# Galileo_Control_Board.net
KiCad netlist of a schematic drawn in Altium Designer
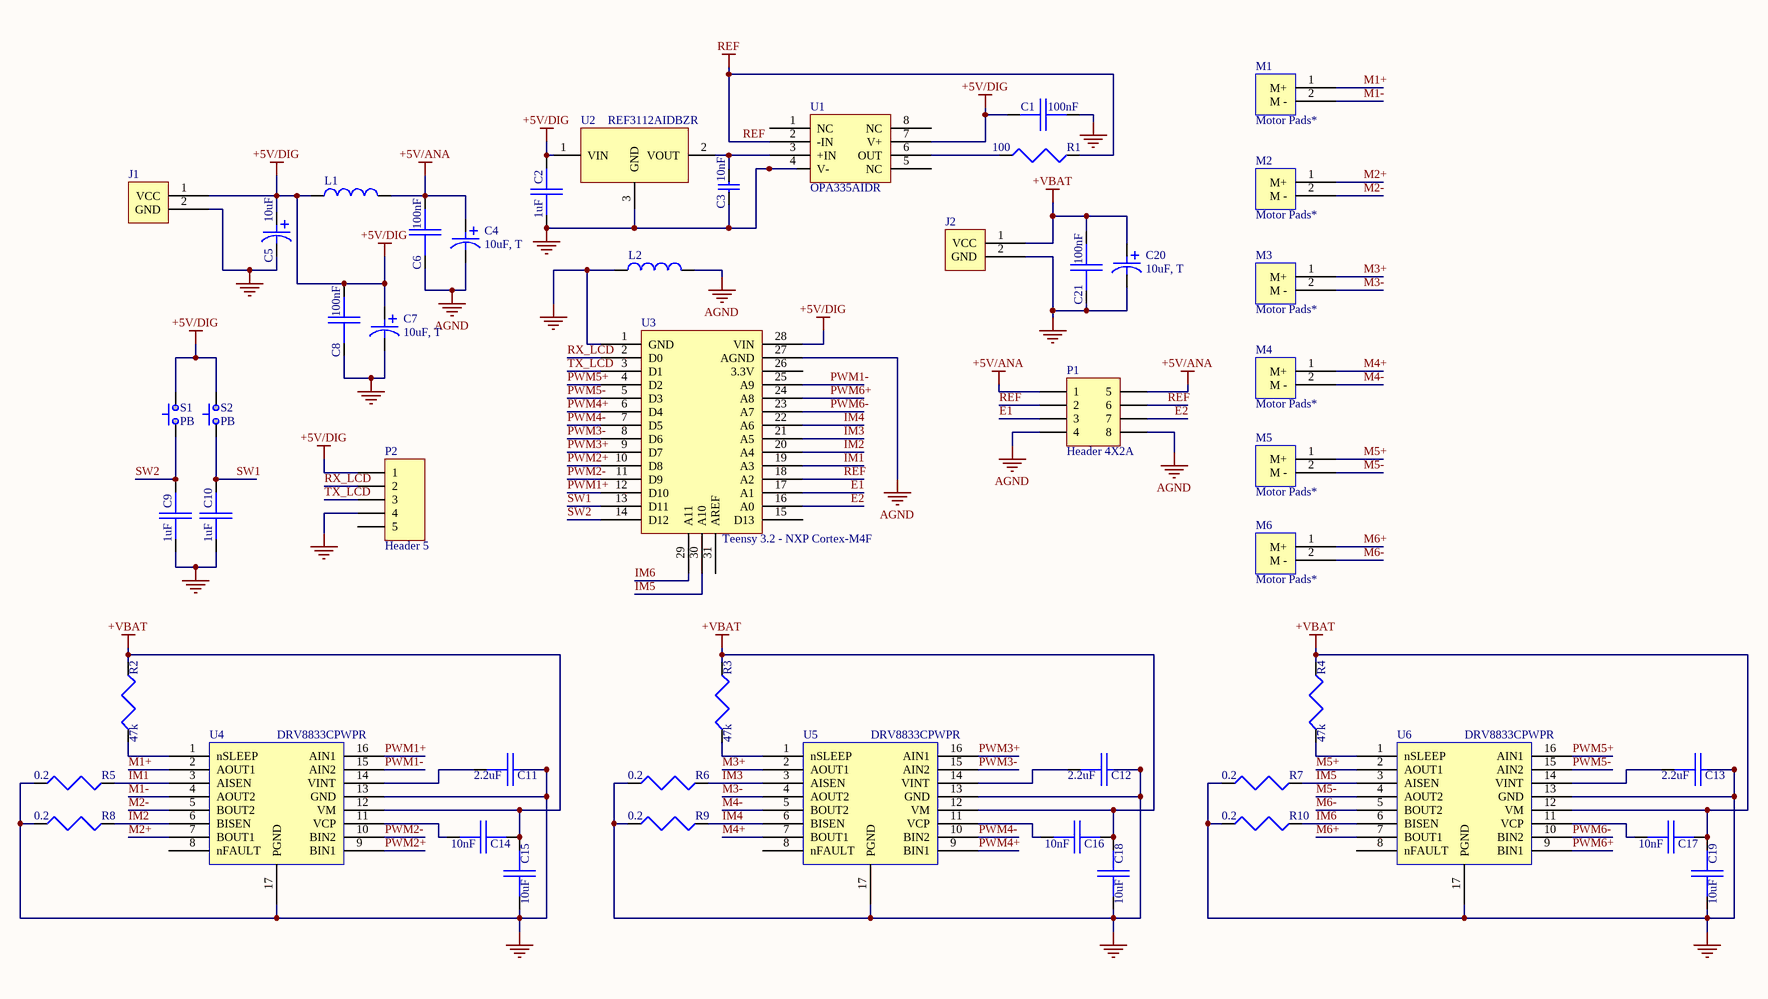
[diagram p0: Galileo_Control_Board.SchDoc]

(export (version "E")
  (design (tool "Eeschema 10.0.6"))
  (components
    (comp (ref "C1")
      (value "100nF")
      (footprint "C0603")
      (description "CAP CER 0.1UF 25V X7R 0603")
      (fields
        (field (name "MANUFACTURER") "Murata Electronics North America")
        (field (name "MANUFACTURER PART NUMBER") "GRM188R71E104KA01D")
      )
      (libsource (lib "EMG") (part "GRM188R71E104KA01D"))
    )
    (comp (ref "C2")
      (value "1uF")
      (footprint "C0603")
      (description "CAP CER 1UF 25V X5R 0603")
      (fields
        (field (name "MANUFACTURER") "Murata Electronics North America")
        (field (name "MANUFACTURER PART NUMBER") "GRM188R61E105KA12D")
      )
      (libsource (lib "EMG") (part "GRM188R61E105KA12D"))
    )
    (comp (ref "C3")
      (value "10nF")
      (footprint "C0805")
      (description "CAP CER 10000PF 50V X7R 0805")
      (fields
        (field (name "MANUFACTURER") "Murata Electronics North America")
        (field (name "MANUFACTURER PART NUMBER") "GRM216R71H103KA01D")
      )
      (libsource (lib "ISL") (part "GRM216R71H103KA01D"))
    )
    (comp (ref "C4")
      (value "10uF, T")
      (footprint "C1206")
      (description "CAP TANT 10UF 20V 10% 2413")
      (fields
        (field (name "MANUFACTURER") "Kemet")
        (field (name "MANUFACTURER PART NUMBER") "T491C106K020AT")
      )
      (libsource (lib "Control") (part "T491C106K020AT"))
    )
    (comp (ref "C5")
      (value "10uF")
      (footprint "CSVB")
      (description "CAP ALUM 10UF 20% 25V SMD")
      (fields
        (field (name "MANUFACTURER") "Panasonic Electronic Components")
        (field (name "MANUFACTURER PART NUMBER") "EEE-1EA100WR")
      )
      (libsource (lib "Control") (part "EEE-1EA100WR"))
    )
    (comp (ref "C6")
      (value "100nF")
      (footprint "C0603")
      (description "CAP CER 0.1UF 25V X7R 0603")
      (fields
        (field (name "MANUFACTURER") "Murata Electronics North America")
        (field (name "MANUFACTURER PART NUMBER") "GRM188R71E104KA01D")
      )
      (libsource (lib "EMG") (part "GRM188R71E104KA01D"))
    )
    (comp (ref "C7")
      (value "10uF, T")
      (footprint "C1206")
      (description "CAP TANT 10UF 20V 10% 2413")
      (fields
        (field (name "MANUFACTURER") "Kemet")
        (field (name "MANUFACTURER PART NUMBER") "T491C106K020AT")
      )
      (libsource (lib "Control") (part "T491C106K020AT"))
    )
    (comp (ref "C8")
      (value "100nF")
      (footprint "C0603")
      (description "CAP CER 0.1UF 25V X7R 0603")
      (fields
        (field (name "MANUFACTURER") "Murata Electronics North America")
        (field (name "MANUFACTURER PART NUMBER") "GRM188R71E104KA01D")
      )
      (libsource (lib "EMG") (part "GRM188R71E104KA01D"))
    )
    (comp (ref "C9")
      (value "1uF")
      (footprint "C0603")
      (description "CAP CER 1UF 25V X5R 0603")
      (fields
        (field (name "MANUFACTURER") "Murata Electronics North America")
        (field (name "MANUFACTURER PART NUMBER") "GRM188R61E105KA12D")
      )
      (libsource (lib "EMG") (part "GRM188R61E105KA12D"))
    )
    (comp (ref "C10")
      (value "1uF")
      (footprint "C0603")
      (description "CAP CER 1UF 25V X5R 0603")
      (fields
        (field (name "MANUFACTURER") "Murata Electronics North America")
        (field (name "MANUFACTURER PART NUMBER") "GRM188R61E105KA12D")
      )
      (libsource (lib "EMG") (part "GRM188R61E105KA12D"))
    )
    (comp (ref "C11")
      (value "2.2uF")
      (footprint "C0603")
      (description "CAP CER 2.2UF 6.3V X5R 0603")
      (fields
        (field (name "MANUFACTURER") "AVX Corporation")
        (field (name "MANUFACTURER PART NUMBER") "06036D225KAT2A")
      )
      (libsource (lib "Galileo_Control_Board") (part "06036D225KAT2A"))
    )
    (comp (ref "C12")
      (value "2.2uF")
      (footprint "C0603")
      (description "CAP CER 2.2UF 6.3V X5R 0603")
      (fields
        (field (name "MANUFACTURER") "AVX Corporation")
        (field (name "MANUFACTURER PART NUMBER") "06036D225KAT2A")
      )
      (libsource (lib "Galileo_Control_Board") (part "06036D225KAT2A"))
    )
    (comp (ref "C13")
      (value "2.2uF")
      (footprint "C0603")
      (description "CAP CER 2.2UF 6.3V X5R 0603")
      (fields
        (field (name "MANUFACTURER") "AVX Corporation")
        (field (name "MANUFACTURER PART NUMBER") "06036D225KAT2A")
      )
      (libsource (lib "Galileo_Control_Board") (part "06036D225KAT2A"))
    )
    (comp (ref "C14")
      (value "10nF")
      (footprint "C0603")
      (description "CAP CER 10000PF 16V X7R 0603")
      (fields
        (field (name "MANUFACTURER") "Kemet")
        (field (name "MANUFACTURER PART NUMBER") "C0603C103K4RACTU")
      )
      (libsource (lib "Galileo_Control_Board") (part "C0603C103K4RACTU"))
    )
    (comp (ref "C15")
      (value "10uF")
      (footprint "C0603")
      (description "CAP CER 10UF 25V X5R 0603")
      (fields
        (field (name "MANUFACTURER") "Murata Electronics North America")
        (field (name "MANUFACTURER PART NUMBER") "GRT188R61E106ME13D")
      )
      (libsource (lib "Galileo_Control_Board") (part "GRT188R61E106ME13D"))
    )
    (comp (ref "C16")
      (value "10nF")
      (footprint "C0603")
      (description "CAP CER 10000PF 16V X7R 0603")
      (fields
        (field (name "MANUFACTURER") "Kemet")
        (field (name "MANUFACTURER PART NUMBER") "C0603C103K4RACTU")
      )
      (libsource (lib "Galileo_Control_Board") (part "C0603C103K4RACTU"))
    )
    (comp (ref "C17")
      (value "10nF")
      (footprint "C0603")
      (description "CAP CER 10000PF 16V X7R 0603")
      (fields
        (field (name "MANUFACTURER") "Kemet")
        (field (name "MANUFACTURER PART NUMBER") "C0603C103K4RACTU")
      )
      (libsource (lib "Galileo_Control_Board") (part "C0603C103K4RACTU"))
    )
    (comp (ref "C18")
      (value "10uF")
      (footprint "C0603")
      (description "CAP CER 10UF 25V X5R 0603")
      (fields
        (field (name "MANUFACTURER") "Murata Electronics North America")
        (field (name "MANUFACTURER PART NUMBER") "GRT188R61E106ME13D")
      )
      (libsource (lib "Galileo_Control_Board") (part "GRT188R61E106ME13D"))
    )
    (comp (ref "C19")
      (value "10uF")
      (footprint "C0603")
      (description "CAP CER 10UF 25V X5R 0603")
      (fields
        (field (name "MANUFACTURER") "Murata Electronics North America")
        (field (name "MANUFACTURER PART NUMBER") "GRT188R61E106ME13D")
      )
      (libsource (lib "Galileo_Control_Board") (part "GRT188R61E106ME13D"))
    )
    (comp (ref "C20")
      (value "10uF, T")
      (footprint "C1206")
      (description "CAP TANT 10UF 20V 10% 2413")
      (fields
        (field (name "MANUFACTURER") "Kemet")
        (field (name "MANUFACTURER PART NUMBER") "T491C106K020AT")
      )
      (libsource (lib "Control") (part "T491C106K020AT"))
    )
    (comp (ref "C21")
      (value "100nF")
      (footprint "C0603")
      (description "CAP CER 0.1UF 25V X7R 0603")
      (fields
        (field (name "MANUFACTURER") "Murata Electronics North America")
        (field (name "MANUFACTURER PART NUMBER") "GRM188R71E104KA01D")
      )
      (libsource (lib "EMG") (part "GRM188R71E104KA01D"))
    )
    (comp (ref "J1")
      (value "TERMINAL BLOCK  2POS 3.5MM")
      (footprint "2POS3.5mm")
      (description "CONN TERMINAL BLOCK 2POS 3.5MM")
      (fields
        (field (name "MANUFACTURER") "Molex, LLC")
        (field (name "MANUFACTURER PART NUMBER") "0393570002")
      )
      (libsource (lib "Control") (part "0393570002"))
    )
    (comp (ref "J2")
      (value "TERMINAL BLOCK  2POS 3.5MM")
      (footprint "2POS3.5mm")
      (description "CONN TERMINAL BLOCK 2POS 3.5MM")
      (fields
        (field (name "MANUFACTURER") "Molex, LLC")
        (field (name "MANUFACTURER PART NUMBER") "0393570002")
      )
      (libsource (lib "Control") (part "0393570002"))
    )
    (comp (ref "L1")
      (value "EMI FILTER BED")
      (footprint "R0603")
      (description "FERRITE BEAD 470 OHM 0603")
      (fields
        (field (name "MANUFACTURER") "Murata Electronics North America")
        (field (name "MANUFACTURER PART NUMBER") "BLM18PG471SN1D")
      )
      (libsource (lib "Control") (part "BLM18PG471SN1D"))
    )
    (comp (ref "L2")
      (value "EMI FILTER BED")
      (footprint "R0603")
      (description "FERRITE BEAD 470 OHM 0603")
      (fields
        (field (name "MANUFACTURER") "Murata Electronics North America")
        (field (name "MANUFACTURER PART NUMBER") "BLM18PG471SN1D")
      )
      (libsource (lib "Control") (part "BLM18PG471SN1D"))
    )
    (comp (ref "M1")
      (value "Motor Pads*")
      (footprint "Motor_PAD")
      (fields
        (field (name "MANUFACTURER") "Portescap")
        (field (name "MANUFACTURER PART NUMBER") "22N1R78313P1001")
      )
      (libsource (lib "Galileo_Control_Board") (part "Motor_PADs"))
    )
    (comp (ref "M2")
      (value "Motor Pads*")
      (footprint "Motor_PAD")
      (fields
        (field (name "MANUFACTURER") "Portescap")
        (field (name "MANUFACTURER PART NUMBER") "22N1R78313P1001")
      )
      (libsource (lib "Galileo_Control_Board") (part "Motor_PADs"))
    )
    (comp (ref "M3")
      (value "Motor Pads*")
      (footprint "Motor_PAD")
      (fields
        (field (name "MANUFACTURER") "Portescap")
        (field (name "MANUFACTURER PART NUMBER") "22N1R78313P1001")
      )
      (libsource (lib "Galileo_Control_Board") (part "Motor_PADs"))
    )
    (comp (ref "M4")
      (value "Motor Pads*")
      (footprint "Motor_PAD")
      (fields
        (field (name "MANUFACTURER") "Portescap")
        (field (name "MANUFACTURER PART NUMBER") "22N1R78313P1001")
      )
      (libsource (lib "Galileo_Control_Board") (part "Motor_PADs"))
    )
    (comp (ref "M5")
      (value "Motor Pads*")
      (footprint "Motor_PAD")
      (fields
        (field (name "MANUFACTURER") "Portescap")
        (field (name "MANUFACTURER PART NUMBER") "22N1R78313P1001")
      )
      (libsource (lib "Galileo_Control_Board") (part "Motor_PADs"))
    )
    (comp (ref "M6")
      (value "Motor Pads*")
      (footprint "Motor_PAD")
      (fields
        (field (name "MANUFACTURER") "Portescap")
        (field (name "MANUFACTURER PART NUMBER") "22N1R78313P1001")
      )
      (libsource (lib "Galileo_Control_Board") (part "Motor_PADs"))
    )
    (comp (ref "P1")
      (value "Header 4X2A")
      (footprint "HDR2X4_CEN")
      (description "Header, 4-Pin, Dual row")
      (fields (field (name "PUBLISHER") "Altium Limited"))
      (libsource (lib "Miscellaneous Connectors") (part "Header 4X2A"))
    )
    (comp (ref "P2")
      (value "Header 5")
      (footprint "HDR1X5")
      (description "Header, 5-Pin")
      (fields (field (name "PUBLISHER") "Altium Limited"))
      (libsource (lib "Miscellaneous Connectors") (part "Header 5"))
    )
    (comp (ref "R1")
      (value "100")
      (footprint "R0603")
      (description "RES SMD 100 OHM 1% 1/10W 0603")
      (fields
        (field (name "MANUFACTURER") "Panasonic Electronic Components")
        (field (name "MANUFACTURER PART NUMBER") "ERJ-3EKF1000V")
      )
      (libsource (lib "EMG") (part "ERJ-3EKF1000V"))
    )
    (comp (ref "R2")
      (value "47k")
      (footprint "R0603")
      (description "RES SMD 47K OHM 1% 1/10W 0603")
      (fields
        (field (name "MANUFACTURER") "Panasonic Electronic Components")
        (field (name "MANUFACTURER PART NUMBER") "ERJ-3EKF4702V")
      )
      (libsource (lib "Galileo_Control_Board") (part "ERJ-3EKF4702V"))
    )
    (comp (ref "R3")
      (value "47k")
      (footprint "R0603")
      (description "RES SMD 47K OHM 1% 1/10W 0603")
      (fields
        (field (name "MANUFACTURER") "Panasonic Electronic Components")
        (field (name "MANUFACTURER PART NUMBER") "ERJ-3EKF4702V")
      )
      (libsource (lib "Galileo_Control_Board") (part "ERJ-3EKF4702V"))
    )
    (comp (ref "R4")
      (value "47k")
      (footprint "R0603")
      (description "RES SMD 47K OHM 1% 1/10W 0603")
      (fields
        (field (name "MANUFACTURER") "Panasonic Electronic Components")
        (field (name "MANUFACTURER PART NUMBER") "ERJ-3EKF4702V")
      )
      (libsource (lib "Galileo_Control_Board") (part "ERJ-3EKF4702V"))
    )
    (comp (ref "R5")
      (value "0.2")
      (footprint "R1206")
      (description "RES SMD 0.2 OHM 5% 1/2W 1206")
      (fields
        (field (name "MANUFACTURER") "Panasonic Electronic Components")
        (field (name "MANUFACTURER PART NUMBER") "ERJ-8BSJR20V")
      )
      (libsource (lib "Galileo_Control_Board") (part "ERJ-8BSJR20V"))
    )
    (comp (ref "R6")
      (value "0.2")
      (footprint "R1206")
      (description "RES SMD 0.2 OHM 5% 1/2W 1206")
      (fields
        (field (name "MANUFACTURER") "Panasonic Electronic Components")
        (field (name "MANUFACTURER PART NUMBER") "ERJ-8BSJR20V")
      )
      (libsource (lib "Galileo_Control_Board") (part "ERJ-8BSJR20V"))
    )
    (comp (ref "R7")
      (value "0.2")
      (footprint "R1206")
      (description "RES SMD 0.2 OHM 5% 1/2W 1206")
      (fields
        (field (name "MANUFACTURER") "Panasonic Electronic Components")
        (field (name "MANUFACTURER PART NUMBER") "ERJ-8BSJR20V")
      )
      (libsource (lib "Galileo_Control_Board") (part "ERJ-8BSJR20V"))
    )
    (comp (ref "R8")
      (value "0.2")
      (footprint "R1206")
      (description "RES SMD 0.2 OHM 5% 1/2W 1206")
      (fields
        (field (name "MANUFACTURER") "Panasonic Electronic Components")
        (field (name "MANUFACTURER PART NUMBER") "ERJ-8BSJR20V")
      )
      (libsource (lib "Galileo_Control_Board") (part "ERJ-8BSJR20V"))
    )
    (comp (ref "R9")
      (value "0.2")
      (footprint "R1206")
      (description "RES SMD 0.2 OHM 5% 1/2W 1206")
      (fields
        (field (name "MANUFACTURER") "Panasonic Electronic Components")
        (field (name "MANUFACTURER PART NUMBER") "ERJ-8BSJR20V")
      )
      (libsource (lib "Galileo_Control_Board") (part "ERJ-8BSJR20V"))
    )
    (comp (ref "R10")
      (value "0.2")
      (footprint "R1206")
      (description "RES SMD 0.2 OHM 5% 1/2W 1206")
      (fields
        (field (name "MANUFACTURER") "Panasonic Electronic Components")
        (field (name "MANUFACTURER PART NUMBER") "ERJ-8BSJR20V")
      )
      (libsource (lib "Galileo_Control_Board") (part "ERJ-8BSJR20V"))
    )
    (comp (ref "S1")
      (value "PB")
      (footprint "SW")
      (description "SWITCH PUSH SPST-NO 0.1A 32V")
      (fields
        (field (name "MANUFACTURER") "C&K Components")
        (field (name "MANUFACTURER PART NUMBER") "D6C90 F1 LFS")
      )
      (libsource (lib "Control") (part "D6C90 F1 LFS"))
    )
    (comp (ref "S2")
      (value "PB")
      (footprint "SW")
      (description "SWITCH PUSH SPST-NO 0.1A 32V")
      (fields
        (field (name "MANUFACTURER") "C&K Components")
        (field (name "MANUFACTURER PART NUMBER") "D6C90 F1 LFS")
      )
      (libsource (lib "Control") (part "D6C90 F1 LFS"))
    )
    (comp (ref "U1")
      (value "OPA335AIDR")
      (footprint "SO-8")
      (description "IC OPAMP CHOPPER 2MHZ RRO 8SOIC")
      (fields (field (name "MANUFACTURER") "Texas Instruments"))
      (libsource (lib "DCDC") (part "OPA335AIDR"))
    )
    (comp (ref "U2")
      (value "REF3112AIDBZR")
      (footprint "SOT-23")
      (description "IC VREF SERIES 1.25V SOT23-3")
      (fields (field (name "MANUFACTURER") "Texas Instruments") (field (name "TOLERANCE") "±0.2%"))
      (libsource (lib "DCDC") (part "REF3112AIDBZR"))
    )
    (comp (ref "U3")
      (value "Teensy 3.2 - NXP Cortex-M4F")
      (footprint "DIP28")
      (fields
        (field (name "MANUFACTURER") "SparkFun Electronics")
        (field (name "MANUFACTURER PART NUMBER") "DEV-13305")
      )
      (libsource (lib "Control") (part "Teensy"))
    )
    (comp (ref "U4")
      (value "DRV8833CPWPR")
      (footprint "SOP16")
      (description "IC MOTOR DRIVER PAR")
      (fields (field (name "MANUFACTURER") "Texas Instruments"))
      (libsource (lib "Galileo_Control_Board") (part "DRV8833CPWPR"))
    )
    (comp (ref "U5")
      (value "DRV8833CPWPR")
      (footprint "SOP16")
      (description "IC MOTOR DRIVER PAR")
      (fields (field (name "MANUFACTURER") "Texas Instruments"))
      (libsource (lib "Galileo_Control_Board") (part "DRV8833CPWPR"))
    )
    (comp (ref "U6")
      (value "DRV8833CPWPR")
      (footprint "SOP16")
      (description "IC MOTOR DRIVER PAR")
      (fields (field (name "MANUFACTURER") "Texas Instruments"))
      (libsource (lib "Galileo_Control_Board") (part "DRV8833CPWPR"))
    )
  )
  (nets
    (net (code "1") (name "+5V{slash}ANA") (class "Default")
      (node (ref "C4") (pin "1") (pinfunction "1_1") (pintype "passive"))
      (node (ref "C6") (pin "2") (pinfunction "2_2") (pintype "passive"))
      (node (ref "L1") (pin "2") (pinfunction "2_2") (pintype "passive"))
      (node (ref "P1") (pin "1") (pinfunction "1_1") (pintype "passive"))
      (node (ref "P1") (pin "5") (pinfunction "5_5") (pintype "passive"))
    )
    (net (code "2") (name "+5V{slash}DIG") (class "Default")
      (node (ref "C1") (pin "2") (pinfunction "2_2") (pintype "passive"))
      (node (ref "C2") (pin "2") (pinfunction "2_2") (pintype "passive"))
      (node (ref "C5") (pin "1") (pinfunction "1_1") (pintype "passive"))
      (node (ref "C7") (pin "1") (pinfunction "1_1") (pintype "passive"))
      (node (ref "C8") (pin "2") (pinfunction "2_2") (pintype "passive"))
      (node (ref "J1") (pin "1") (pinfunction "VCC_1") (pintype "passive"))
      (node (ref "L1") (pin "1") (pinfunction "1_1") (pintype "passive"))
      (node (ref "P2") (pin "1") (pinfunction "1_1") (pintype "passive"))
      (node (ref "S1") (pin "2") (pinfunction "2_2") (pintype "passive"))
      (node (ref "S2") (pin "2") (pinfunction "2_2") (pintype "passive"))
      (node (ref "U1") (pin "7") (pinfunction "V+_7") (pintype "passive"))
      (node (ref "U2") (pin "1") (pinfunction "VIN_1") (pintype "passive"))
      (node (ref "U3") (pin "28") (pinfunction "VIN_28") (pintype "passive"))
    )
    (net (code "3") (name "+VBAT") (class "Default")
      (node (ref "C14") (pin "2") (pinfunction "2_2") (pintype "passive"))
      (node (ref "C15") (pin "2") (pinfunction "2_2") (pintype "passive"))
      (node (ref "C16") (pin "2") (pinfunction "2_2") (pintype "passive"))
      (node (ref "C17") (pin "2") (pinfunction "2_2") (pintype "passive"))
      (node (ref "C18") (pin "2") (pinfunction "2_2") (pintype "passive"))
      (node (ref "C19") (pin "2") (pinfunction "2_2") (pintype "passive"))
      (node (ref "C20") (pin "1") (pinfunction "1_1") (pintype "passive"))
      (node (ref "C21") (pin "2") (pinfunction "2_2") (pintype "passive"))
      (node (ref "J2") (pin "1") (pinfunction "VCC_1") (pintype "passive"))
      (node (ref "R2") (pin "2") (pinfunction "2_2") (pintype "passive"))
      (node (ref "R3") (pin "2") (pinfunction "2_2") (pintype "passive"))
      (node (ref "R4") (pin "2") (pinfunction "2_2") (pintype "passive"))
      (node (ref "U4") (pin "12") (pinfunction "VM_12") (pintype "passive"))
      (node (ref "U5") (pin "12") (pinfunction "VM_12") (pintype "passive"))
      (node (ref "U6") (pin "12") (pinfunction "VM_12") (pintype "passive"))
    )
    (net (code "4") (name "/E1") (class "Default")
      (node (ref "P1") (pin "3") (pinfunction "3_3") (pintype "passive"))
      (node (ref "U3") (pin "17") (pinfunction "A1_17") (pintype "passive"))
    )
    (net (code "5") (name "/E2") (class "Default")
      (node (ref "P1") (pin "7") (pinfunction "7_7") (pintype "passive"))
      (node (ref "U3") (pin "16") (pinfunction "A0_16") (pintype "passive"))
    )
    (net (code "6") (name "/IM1") (class "Default")
      (node (ref "R5") (pin "2") (pinfunction "2_2") (pintype "passive"))
      (node (ref "U3") (pin "19") (pinfunction "A3_19") (pintype "passive"))
      (node (ref "U4") (pin "3") (pinfunction "AISEN_3") (pintype "passive"))
    )
    (net (code "7") (name "/IM2") (class "Default")
      (node (ref "R8") (pin "2") (pinfunction "2_2") (pintype "passive"))
      (node (ref "U3") (pin "20") (pinfunction "A4_20") (pintype "passive"))
      (node (ref "U4") (pin "6") (pinfunction "BISEN_6") (pintype "passive"))
    )
    (net (code "8") (name "/IM3") (class "Default")
      (node (ref "R6") (pin "2") (pinfunction "2_2") (pintype "passive"))
      (node (ref "U3") (pin "21") (pinfunction "A5_21") (pintype "passive"))
      (node (ref "U5") (pin "3") (pinfunction "AISEN_3") (pintype "passive"))
    )
    (net (code "9") (name "/IM4") (class "Default")
      (node (ref "R9") (pin "2") (pinfunction "2_2") (pintype "passive"))
      (node (ref "U3") (pin "22") (pinfunction "A6_22") (pintype "passive"))
      (node (ref "U5") (pin "6") (pinfunction "BISEN_6") (pintype "passive"))
    )
    (net (code "10") (name "/IM5") (class "Default")
      (node (ref "R7") (pin "2") (pinfunction "2_2") (pintype "passive"))
      (node (ref "U3") (pin "30") (pinfunction "A10_30") (pintype "passive"))
      (node (ref "U6") (pin "3") (pinfunction "AISEN_3") (pintype "passive"))
    )
    (net (code "11") (name "/IM6") (class "Default")
      (node (ref "R10") (pin "2") (pinfunction "2_2") (pintype "passive"))
      (node (ref "U3") (pin "29") (pinfunction "A11_29") (pintype "passive"))
      (node (ref "U6") (pin "6") (pinfunction "BISEN_6") (pintype "passive"))
    )
    (net (code "12") (name "/M1+") (class "Default")
      (node (ref "M1") (pin "1") (pinfunction "M+_1") (pintype "passive"))
      (node (ref "U4") (pin "2") (pinfunction "AOUT1_2") (pintype "passive"))
    )
    (net (code "13") (name "/M1-") (class "Default")
      (node (ref "M1") (pin "2") (pinfunction "M_-_2") (pintype "passive"))
      (node (ref "U4") (pin "4") (pinfunction "AOUT2_4") (pintype "passive"))
    )
    (net (code "14") (name "/M2+") (class "Default")
      (node (ref "M2") (pin "1") (pinfunction "M+_1") (pintype "passive"))
      (node (ref "U4") (pin "7") (pinfunction "BOUT1_7") (pintype "passive"))
    )
    (net (code "15") (name "/M2-") (class "Default")
      (node (ref "M2") (pin "2") (pinfunction "M_-_2") (pintype "passive"))
      (node (ref "U4") (pin "5") (pinfunction "BOUT2_5") (pintype "passive"))
    )
    (net (code "16") (name "/M3+") (class "Default")
      (node (ref "M3") (pin "1") (pinfunction "M+_1") (pintype "passive"))
      (node (ref "U5") (pin "2") (pinfunction "AOUT1_2") (pintype "passive"))
    )
    (net (code "17") (name "/M3-") (class "Default")
      (node (ref "M3") (pin "2") (pinfunction "M_-_2") (pintype "passive"))
      (node (ref "U5") (pin "4") (pinfunction "AOUT2_4") (pintype "passive"))
    )
    (net (code "18") (name "/M4+") (class "Default")
      (node (ref "M4") (pin "1") (pinfunction "M+_1") (pintype "passive"))
      (node (ref "U5") (pin "7") (pinfunction "BOUT1_7") (pintype "passive"))
    )
    (net (code "19") (name "/M4-") (class "Default")
      (node (ref "M4") (pin "2") (pinfunction "M_-_2") (pintype "passive"))
      (node (ref "U5") (pin "5") (pinfunction "BOUT2_5") (pintype "passive"))
    )
    (net (code "20") (name "/M5+") (class "Default")
      (node (ref "M5") (pin "1") (pinfunction "M+_1") (pintype "passive"))
      (node (ref "U6") (pin "2") (pinfunction "AOUT1_2") (pintype "passive"))
    )
    (net (code "21") (name "/M5-") (class "Default")
      (node (ref "M5") (pin "2") (pinfunction "M_-_2") (pintype "passive"))
      (node (ref "U6") (pin "4") (pinfunction "AOUT2_4") (pintype "passive"))
    )
    (net (code "22") (name "/M6+") (class "Default")
      (node (ref "M6") (pin "1") (pinfunction "M+_1") (pintype "passive"))
      (node (ref "U6") (pin "7") (pinfunction "BOUT1_7") (pintype "passive"))
    )
    (net (code "23") (name "/M6-") (class "Default")
      (node (ref "M6") (pin "2") (pinfunction "M_-_2") (pintype "passive"))
      (node (ref "U6") (pin "5") (pinfunction "BOUT2_5") (pintype "passive"))
    )
    (net (code "24") (name "/PWM1+") (class "Default")
      (node (ref "U3") (pin "12") (pinfunction "D10_12") (pintype "passive"))
      (node (ref "U4") (pin "16") (pinfunction "AIN1_16") (pintype "passive"))
    )
    (net (code "25") (name "/PWM1-") (class "Default")
      (node (ref "U3") (pin "25") (pinfunction "A9_25") (pintype "passive"))
      (node (ref "U4") (pin "15") (pinfunction "AIN2_15") (pintype "passive"))
    )
    (net (code "26") (name "/PWM2+") (class "Default")
      (node (ref "U3") (pin "10") (pinfunction "D8_10") (pintype "passive"))
      (node (ref "U4") (pin "9") (pinfunction "BIN1_9") (pintype "passive"))
    )
    (net (code "27") (name "/PWM2-") (class "Default")
      (node (ref "U3") (pin "11") (pinfunction "D9_11") (pintype "passive"))
      (node (ref "U4") (pin "10") (pinfunction "BIN2_10") (pintype "passive"))
    )
    (net (code "28") (name "/PWM3+") (class "Default")
      (node (ref "U3") (pin "9") (pinfunction "D7_9") (pintype "passive"))
      (node (ref "U5") (pin "16") (pinfunction "AIN1_16") (pintype "passive"))
    )
    (net (code "29") (name "/PWM3-") (class "Default")
      (node (ref "U3") (pin "8") (pinfunction "D6_8") (pintype "passive"))
      (node (ref "U5") (pin "15") (pinfunction "AIN2_15") (pintype "passive"))
    )
    (net (code "30") (name "/PWM4+") (class "Default")
      (node (ref "U3") (pin "6") (pinfunction "D4_6") (pintype "passive"))
      (node (ref "U5") (pin "9") (pinfunction "BIN1_9") (pintype "passive"))
    )
    (net (code "31") (name "/PWM4-") (class "Default")
      (node (ref "U3") (pin "7") (pinfunction "D5_7") (pintype "passive"))
      (node (ref "U5") (pin "10") (pinfunction "BIN2_10") (pintype "passive"))
    )
    (net (code "32") (name "/PWM5+") (class "Default")
      (node (ref "U3") (pin "4") (pinfunction "D2_4") (pintype "passive"))
      (node (ref "U6") (pin "16") (pinfunction "AIN1_16") (pintype "passive"))
    )
    (net (code "33") (name "/PWM5-") (class "Default")
      (node (ref "U3") (pin "5") (pinfunction "D3_5") (pintype "passive"))
      (node (ref "U6") (pin "15") (pinfunction "AIN2_15") (pintype "passive"))
    )
    (net (code "34") (name "/PWM6+") (class "Default")
      (node (ref "U3") (pin "24") (pinfunction "A8_24") (pintype "passive"))
      (node (ref "U6") (pin "9") (pinfunction "BIN1_9") (pintype "passive"))
    )
    (net (code "35") (name "/PWM6-") (class "Default")
      (node (ref "U3") (pin "23") (pinfunction "A7_23") (pintype "passive"))
      (node (ref "U6") (pin "10") (pinfunction "BIN2_10") (pintype "passive"))
    )
    (net (code "36") (name "/RX_LCD") (class "Default")
      (node (ref "P2") (pin "2") (pinfunction "2_2") (pintype "passive"))
      (node (ref "U3") (pin "2") (pinfunction "D0_2") (pintype "passive"))
    )
    (net (code "37") (name "/SW1") (class "Default")
      (node (ref "C10") (pin "2") (pinfunction "2_2") (pintype "passive"))
      (node (ref "S2") (pin "1") (pinfunction "1_1") (pintype "passive"))
      (node (ref "U3") (pin "13") (pinfunction "D11_13") (pintype "passive"))
    )
    (net (code "38") (name "/SW2") (class "Default")
      (node (ref "C9") (pin "2") (pinfunction "2_2") (pintype "passive"))
      (node (ref "S1") (pin "1") (pinfunction "1_1") (pintype "passive"))
      (node (ref "U3") (pin "14") (pinfunction "D12_14") (pintype "passive"))
    )
    (net (code "39") (name "/TX_LCD") (class "Default")
      (node (ref "P2") (pin "3") (pinfunction "3_3") (pintype "passive"))
      (node (ref "U3") (pin "3") (pinfunction "D1_3") (pintype "passive"))
    )
    (net (code "40") (name "AGND") (class "Default")
      (node (ref "C4") (pin "2") (pinfunction "2_2") (pintype "passive"))
      (node (ref "C6") (pin "1") (pinfunction "1_1") (pintype "passive"))
      (node (ref "L2") (pin "2") (pinfunction "2_2") (pintype "passive"))
      (node (ref "P1") (pin "4") (pinfunction "4_4") (pintype "passive"))
      (node (ref "P1") (pin "8") (pinfunction "8_8") (pintype "passive"))
      (node (ref "U3") (pin "27") (pinfunction "AGND_27") (pintype "passive"))
    )
    (net (code "41") (name "GND") (class "Default")
      (node (ref "C1") (pin "1") (pinfunction "1_1") (pintype "passive"))
      (node (ref "C10") (pin "1") (pinfunction "1_1") (pintype "passive"))
      (node (ref "C11") (pin "2") (pinfunction "2_2") (pintype "passive"))
      (node (ref "C12") (pin "2") (pinfunction "2_2") (pintype "passive"))
      (node (ref "C13") (pin "2") (pinfunction "2_2") (pintype "passive"))
      (node (ref "C15") (pin "1") (pinfunction "1_1") (pintype "passive"))
      (node (ref "C18") (pin "1") (pinfunction "1_1") (pintype "passive"))
      (node (ref "C19") (pin "1") (pinfunction "1_1") (pintype "passive"))
      (node (ref "C2") (pin "1") (pinfunction "1_1") (pintype "passive"))
      (node (ref "C20") (pin "2") (pinfunction "2_2") (pintype "passive"))
      (node (ref "C21") (pin "1") (pinfunction "1_1") (pintype "passive"))
      (node (ref "C3") (pin "1") (pinfunction "1_1") (pintype "passive"))
      (node (ref "C5") (pin "2") (pinfunction "2_2") (pintype "passive"))
      (node (ref "C7") (pin "2") (pinfunction "2_2") (pintype "passive"))
      (node (ref "C8") (pin "1") (pinfunction "1_1") (pintype "passive"))
      (node (ref "C9") (pin "1") (pinfunction "1_1") (pintype "passive"))
      (node (ref "J1") (pin "2") (pinfunction "GND_2") (pintype "passive"))
      (node (ref "J2") (pin "2") (pinfunction "GND_2") (pintype "passive"))
      (node (ref "L2") (pin "1") (pinfunction "1_1") (pintype "passive"))
      (node (ref "P2") (pin "4") (pinfunction "4_4") (pintype "passive"))
      (node (ref "R10") (pin "1") (pinfunction "1_1") (pintype "passive"))
      (node (ref "R5") (pin "1") (pinfunction "1_1") (pintype "passive"))
      (node (ref "R6") (pin "1") (pinfunction "1_1") (pintype "passive"))
      (node (ref "R7") (pin "1") (pinfunction "1_1") (pintype "passive"))
      (node (ref "R8") (pin "1") (pinfunction "1_1") (pintype "passive"))
      (node (ref "R9") (pin "1") (pinfunction "1_1") (pintype "passive"))
      (node (ref "U1") (pin "4") (pinfunction "V-_4") (pintype "passive"))
      (node (ref "U2") (pin "3") (pinfunction "GND_3") (pintype "passive"))
      (node (ref "U3") (pin "1") (pinfunction "GND_1") (pintype "passive"))
      (node (ref "U4") (pin "13") (pinfunction "GND_13") (pintype "passive"))
      (node (ref "U4") (pin "17") (pinfunction "PGND_17") (pintype "passive"))
      (node (ref "U5") (pin "13") (pinfunction "GND_13") (pintype "passive"))
      (node (ref "U5") (pin "17") (pinfunction "PGND_17") (pintype "passive"))
      (node (ref "U6") (pin "13") (pinfunction "GND_13") (pintype "passive"))
      (node (ref "U6") (pin "17") (pinfunction "PGND_17") (pintype "passive"))
    )
    (net (code "42") (name "Net-(U1-+IN)") (class "Default")
      (node (ref "C3") (pin "2") (pinfunction "2_2") (pintype "passive"))
      (node (ref "U1") (pin "3") (pinfunction "+IN_3") (pintype "passive"))
      (node (ref "U2") (pin "2") (pinfunction "VOUT_2") (pintype "passive"))
    )
    (net (code "43") (name "Net-(U1-OUT)") (class "Default")
      (node (ref "R1") (pin "2") (pinfunction "2_2") (pintype "passive"))
      (node (ref "U1") (pin "6") (pinfunction "OUT_6") (pintype "passive"))
    )
    (net (code "44") (name "Net-(U4-VCP)") (class "Default")
      (node (ref "C14") (pin "1") (pinfunction "1_1") (pintype "passive"))
      (node (ref "U4") (pin "11") (pinfunction "VCP_11") (pintype "passive"))
    )
    (net (code "45") (name "Net-(U4-VINT)") (class "Default")
      (node (ref "C11") (pin "1") (pinfunction "1_1") (pintype "passive"))
      (node (ref "U4") (pin "14") (pinfunction "VINT_14") (pintype "passive"))
    )
    (net (code "46") (name "Net-(U4-nSLEEP)") (class "Default")
      (node (ref "R2") (pin "1") (pinfunction "1_1") (pintype "passive"))
      (node (ref "U4") (pin "1") (pinfunction "nSLEEP_1") (pintype "passive"))
    )
    (net (code "47") (name "Net-(U5-VCP)") (class "Default")
      (node (ref "C16") (pin "1") (pinfunction "1_1") (pintype "passive"))
      (node (ref "U5") (pin "11") (pinfunction "VCP_11") (pintype "passive"))
    )
    (net (code "48") (name "Net-(U5-VINT)") (class "Default")
      (node (ref "C12") (pin "1") (pinfunction "1_1") (pintype "passive"))
      (node (ref "U5") (pin "14") (pinfunction "VINT_14") (pintype "passive"))
    )
    (net (code "49") (name "Net-(U5-nSLEEP)") (class "Default")
      (node (ref "R3") (pin "1") (pinfunction "1_1") (pintype "passive"))
      (node (ref "U5") (pin "1") (pinfunction "nSLEEP_1") (pintype "passive"))
    )
    (net (code "50") (name "Net-(U6-VCP)") (class "Default")
      (node (ref "C17") (pin "1") (pinfunction "1_1") (pintype "passive"))
      (node (ref "U6") (pin "11") (pinfunction "VCP_11") (pintype "passive"))
    )
    (net (code "51") (name "Net-(U6-VINT)") (class "Default")
      (node (ref "C13") (pin "1") (pinfunction "1_1") (pintype "passive"))
      (node (ref "U6") (pin "14") (pinfunction "VINT_14") (pintype "passive"))
    )
    (net (code "52") (name "Net-(U6-nSLEEP)") (class "Default")
      (node (ref "R4") (pin "1") (pinfunction "1_1") (pintype "passive"))
      (node (ref "U6") (pin "1") (pinfunction "nSLEEP_1") (pintype "passive"))
    )
    (net (code "53") (name "REF") (class "Default")
      (node (ref "P1") (pin "2") (pinfunction "2_2") (pintype "passive"))
      (node (ref "P1") (pin "6") (pinfunction "6_6") (pintype "passive"))
      (node (ref "R1") (pin "1") (pinfunction "1_1") (pintype "passive"))
      (node (ref "U1") (pin "2") (pinfunction "-IN_2") (pintype "passive"))
      (node (ref "U3") (pin "18") (pinfunction "A2_18") (pintype "passive"))
    )
    (net (code "54") (name "unconnected-(P2-Pad5)") (class "Default")
      (node (ref "P2") (pin "5") (pinfunction "5_5") (pintype "passive"))
    )
    (net (code "55") (name "unconnected-(U1-NC-Pad1)") (class "Default")
      (node (ref "U1") (pin "1") (pinfunction "NC_1") (pintype "passive"))
    )
    (net (code "56") (name "unconnected-(U1-NC-Pad5)") (class "Default")
      (node (ref "U1") (pin "5") (pinfunction "NC_5") (pintype "passive"))
    )
    (net (code "57") (name "unconnected-(U1-NC-Pad8)") (class "Default")
      (node (ref "U1") (pin "8") (pinfunction "NC_8") (pintype "passive"))
    )
    (net (code "58") (name "unconnected-(U3-3.3V-Pad26)") (class "Default")
      (node (ref "U3") (pin "26") (pinfunction "3.3V_26") (pintype "passive"))
    )
    (net (code "59") (name "unconnected-(U3-AREF-Pad31)") (class "Default")
      (node (ref "U3") (pin "31") (pinfunction "AREF_31") (pintype "passive"))
    )
    (net (code "60") (name "unconnected-(U3-D13-Pad15)") (class "Default")
      (node (ref "U3") (pin "15") (pinfunction "D13_15") (pintype "passive"))
    )
    (net (code "61") (name "unconnected-(U4-nFAULT-Pad8)") (class "Default")
      (node (ref "U4") (pin "8") (pinfunction "nFAULT_8") (pintype "passive"))
    )
    (net (code "62") (name "unconnected-(U5-nFAULT-Pad8)") (class "Default")
      (node (ref "U5") (pin "8") (pinfunction "nFAULT_8") (pintype "passive"))
    )
    (net (code "63") (name "unconnected-(U6-nFAULT-Pad8)") (class "Default")
      (node (ref "U6") (pin "8") (pinfunction "nFAULT_8") (pintype "passive"))
    )
  )
)
